# SCH_AdEMNEA-MAK_2024-02-09.net
KiCad netlist of a schematic drawn in EasyEDA
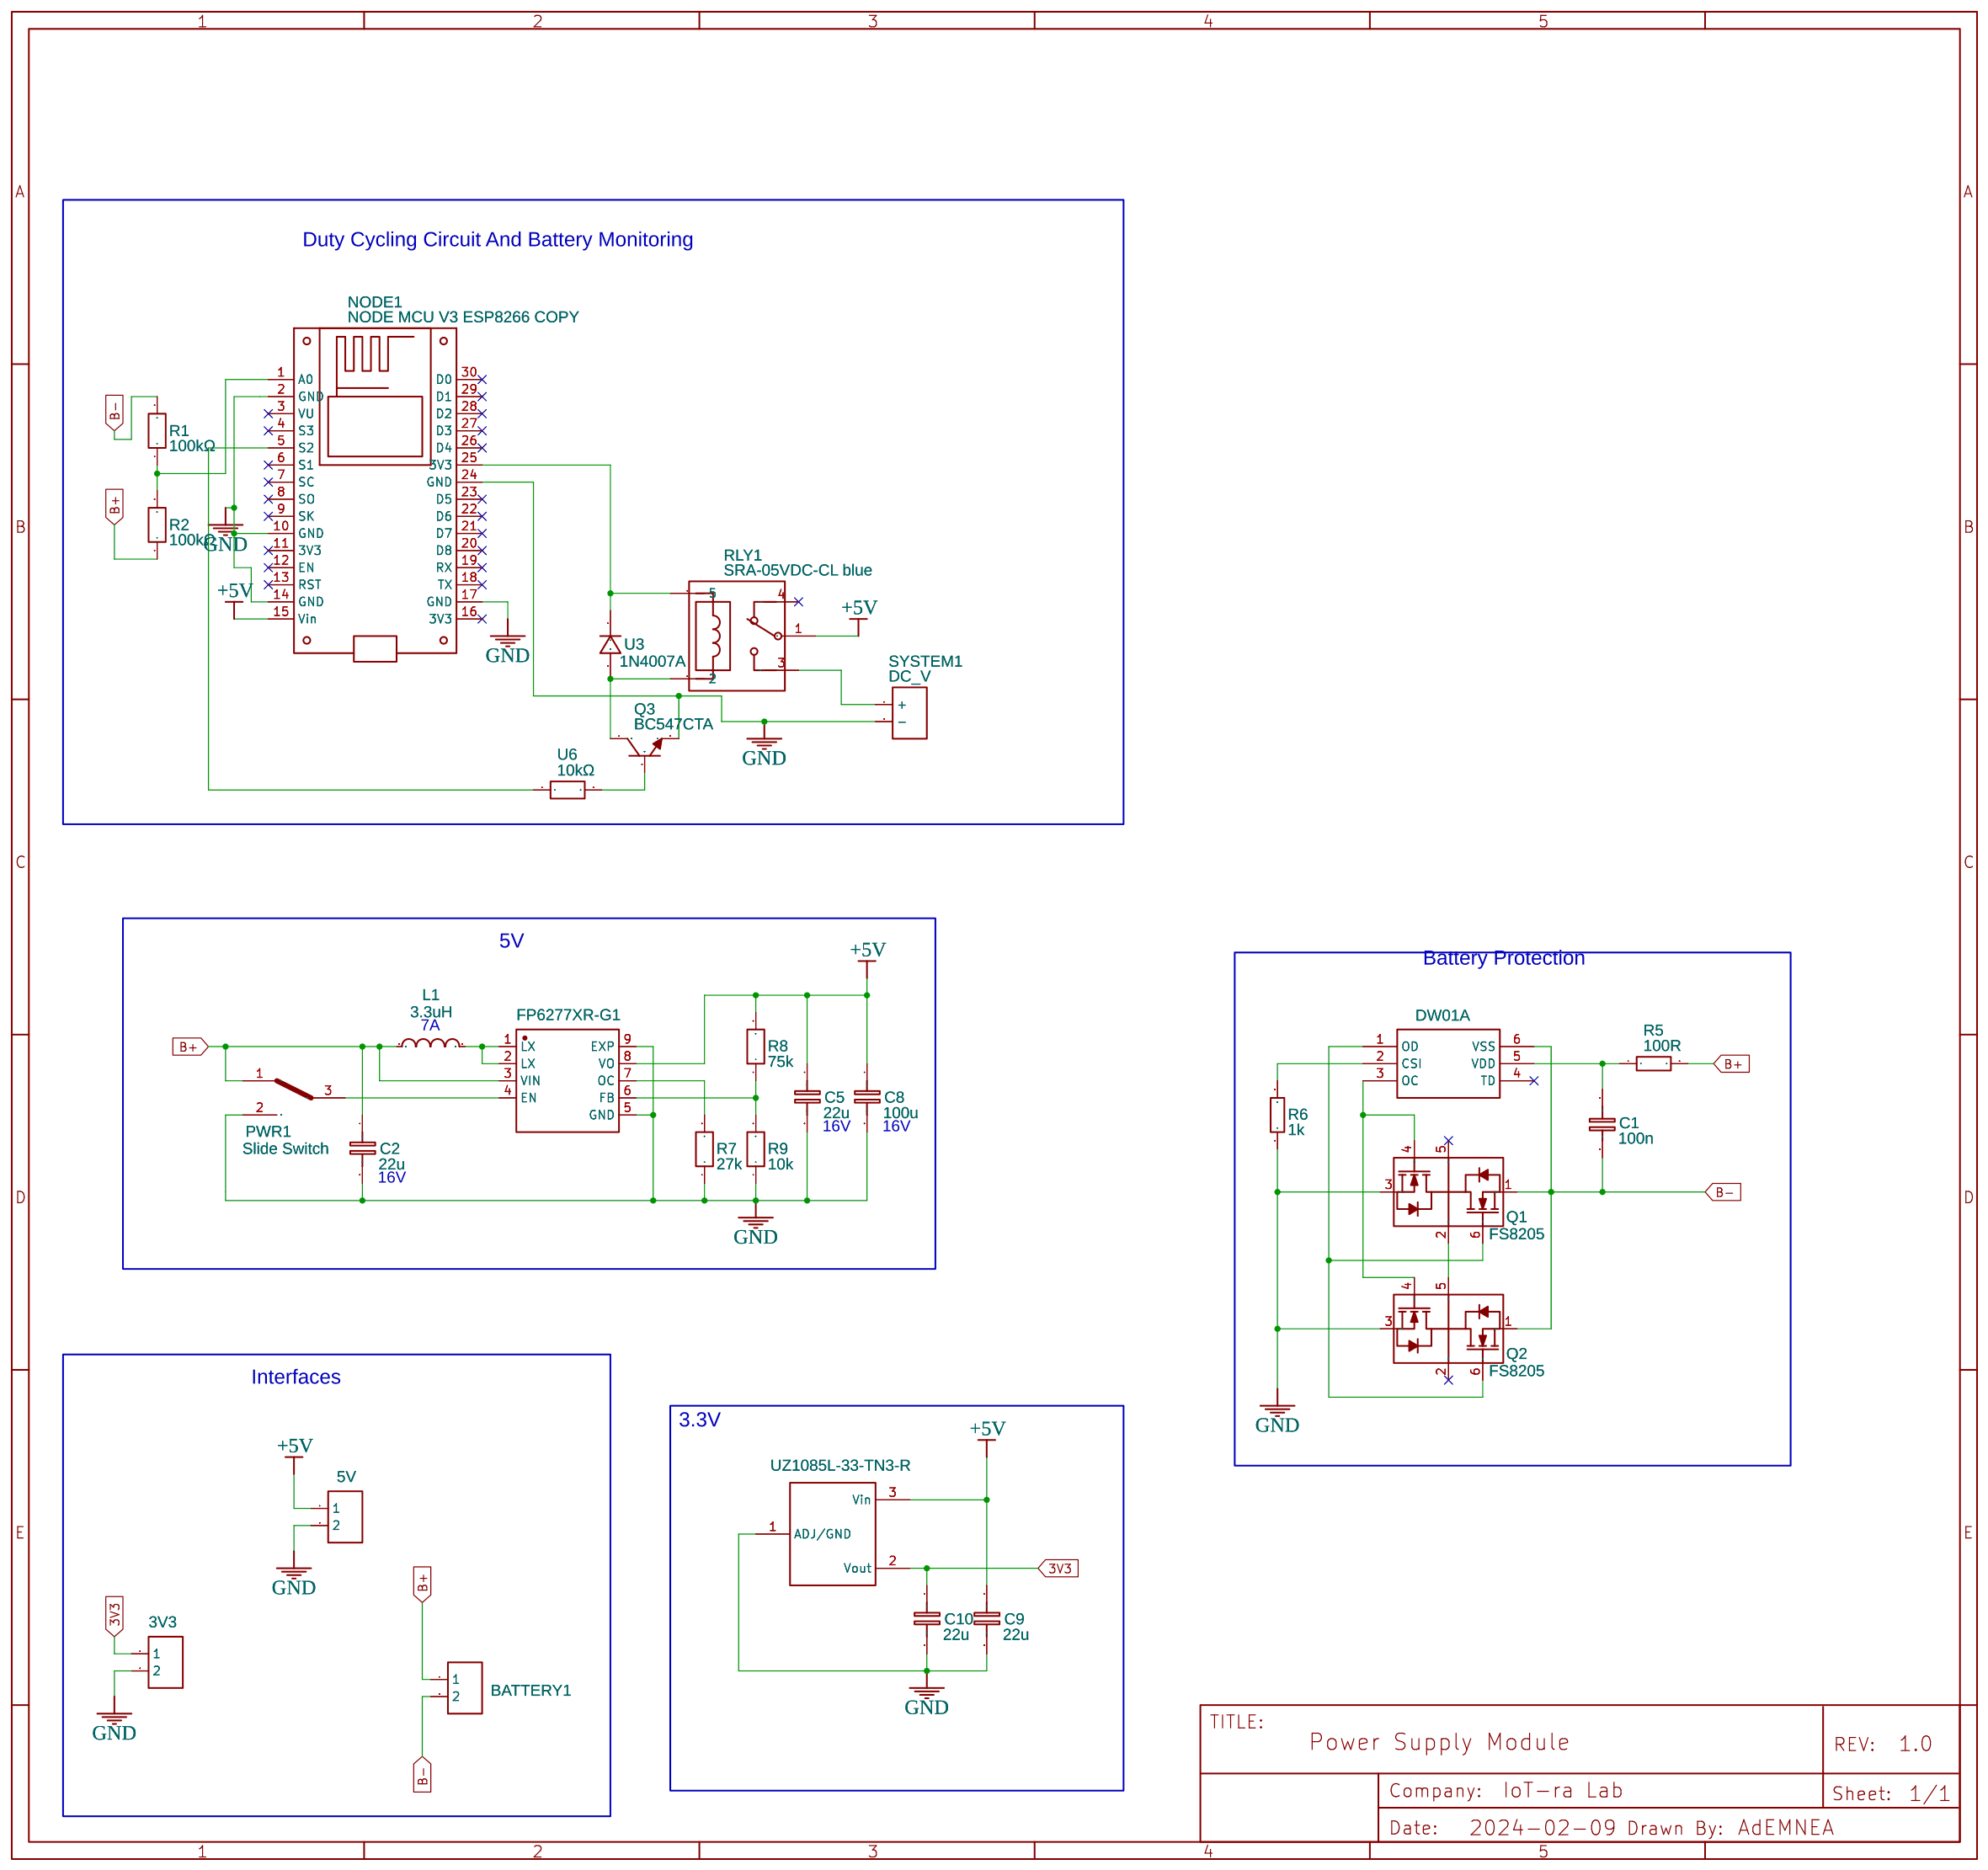
[diagram p0: schematic sheet]

(export (version "E")
  (design (tool "Eeschema 10.0.6"))
  (components
    (comp (ref "3V3")
      (value "Connector")
      (fields (field (name "Manufacturer Part") "2.54-1*2PFemale") (field (name "Manufacturer") "BOOMELE"))
      (libsource (lib "") (part "Unknown_80_-110"))
    )
    (comp (ref "5V")
      (value "Connector")
      (fields (field (name "Manufacturer Part") "2.54-1*2PFemale") (field (name "Manufacturer") "BOOMELE"))
      (libsource (lib "") (part "Unknown_185_-195"))
    )
    (comp (ref "BATTERY1")
      (value "Connector")
      (fields (field (name "Manufacturer Part") "2.54-1*2PFemale") (field (name "Manufacturer") "BOOMELE"))
      (libsource (lib "") (part "Unknown_255_-95"))
    )
    (comp (ref "C1")
      (value "100n")
      (fields (field (name "Manufacturer Part") "CC0805KRX7R9BB104") (field (name "Manufacturer") "YAGEO"))
      (libsource (lib "") (part "Cap_0805_EU_2"))
    )
    (comp (ref "C2")
      (value "22u")
      (fields (field (name "Manufacturer Part") "CL21A226MAQNNNE") (field (name "Manufacturer") "SAMSUNG"))
      (libsource (lib "") (part "Cap_0805_EU"))
    )
    (comp (ref "C5")
      (value "22u")
      (fields (field (name "Manufacturer Part") "CL21A226MAQNNNE") (field (name "Manufacturer") "SAMSUNG"))
      (libsource (lib "") (part "Cap_0805_EU"))
    )
    (comp (ref "C8")
      (value "100u")
      (fields (field (name "Manufacturer Part") "CL31A107MPHNNNE") (field (name "Manufacturer") "SAMSUNG"))
      (libsource (lib "") (part "Cap_0805_EU"))
    )
    (comp (ref "C9")
      (value "22u")
      (fields (field (name "Manufacturer Part") "CL21A226MAQNNNE") (field (name "Manufacturer") "SAMSUNG"))
      (libsource (lib "") (part "Cap_0805_EU_1"))
    )
    (comp (ref "C10")
      (value "22u")
      (fields (field (name "Manufacturer Part") "CL21A226MAQNNNE") (field (name "Manufacturer") "SAMSUNG"))
      (libsource (lib "") (part "Cap_0805_EU_1"))
    )
    (comp (ref "L1")
      (value "3.3uH")
      (fields (field (name "Manufacturer Part") "JSHC0650H-3R3M-G") (field (name "Manufacturer") "Jinlai"))
      (libsource (lib "") (part "JSHC0650H-3R3M-G"))
    )
    (comp (ref "NODE1")
      (value "NODE MCU V3 ESP8266 COPY")
      (libsource (lib "") (part "NODE MCU V3 ESP8266 COPY"))
    )
    (comp (ref "PWR1")
      (value "Slide Switch")
      (fields (field (name "Manufacturer Part") "New SchematicLib"))
      (libsource (lib "") (part "Unknown_160_-440"))
    )
    (comp (ref "Q1")
      (value "FS8205")
      (fields (field (name "Manufacturer") "FORTUNE"))
      (libsource (lib "") (part "FS8205"))
    )
    (comp (ref "Q2")
      (value "FS8205")
      (fields (field (name "Manufacturer") "FORTUNE"))
      (libsource (lib "") (part "FS8205"))
    )
    (comp (ref "Q3")
      (value "BC547CTA")
      (fields (field (name "Manufacturer") "onsemi(安森美)"))
      (libsource (lib "") (part "BC547CTA"))
    )
    (comp (ref "R1")
      (value "100kΩ")
      (fields
        (field (name "Manufacturer Part") "RNF14FAE100K")
        (field (name "Manufacturer") "SEI(Stackpole Electronics Inc.)")
      )
      (libsource (lib "") (part "RNF14FAE100K"))
    )
    (comp (ref "R2")
      (value "100kΩ")
      (fields
        (field (name "Manufacturer Part") "RNF14FAE100K")
        (field (name "Manufacturer") "SEI(Stackpole Electronics Inc.)")
      )
      (libsource (lib "") (part "RNF14FAE100K"))
    )
    (comp (ref "R5")
      (value "100R")
      (fields (field (name "Manufacturer Part") "0805W8F1000T5E") (field (name "Manufacturer") "UniOhm"))
      (libsource (lib "") (part "Res_0805(1/8W)_EU_1"))
    )
    (comp (ref "R6")
      (value "1k")
      (fields (field (name "Manufacturer Part") "0805W8F1001T5E") (field (name "Manufacturer") "UniOhm"))
      (libsource (lib "") (part "Res_0805(1/8W)_EU_2"))
    )
    (comp (ref "R7")
      (value "27k")
      (fields (field (name "Manufacturer Part") "0805W8F2702T5E") (field (name "Manufacturer") "UniOhm"))
      (libsource (lib "") (part "Res_0805(1/8W)_EU"))
    )
    (comp (ref "R8")
      (value "75k")
      (fields (field (name "Manufacturer Part") "0805W8F7502T5E") (field (name "Manufacturer") "UniOhm"))
      (libsource (lib "") (part "Res_0805(1/8W)_EU"))
    )
    (comp (ref "R9")
      (value "10k")
      (fields (field (name "Manufacturer Part") "0805W8F1002T5E") (field (name "Manufacturer") "UniOhm"))
      (libsource (lib "") (part "Res_0805(1/8W)_EU"))
    )
    (comp (ref "RLY1")
      (value "SRA-05VDC-CL blue")
      (fields (field (name "Manufacturer Part") "SRA-05VDC-CL") (field (name "Manufacturer") "松乐"))
      (libsource (lib "") (part "SRA-05VDC-CL blue"))
    )
    (comp (ref "SYSTEM1") (value "DC_V") (libsource (lib "") (part "DC_V")))
    (comp (ref "U1")
      (value "FP6277XR-G1")
      (fields (field (name "Manufacturer") "Feeling Technology"))
      (libsource (lib "") (part "FP6277XR-G1"))
    )
    (comp (ref "U2")
      (value "DW01A")
      (fields (field (name "Manufacturer") "FM"))
      (libsource (lib "") (part "Unknown_835_-460"))
    )
    (comp (ref "U3")
      (value "1N4007A")
      (fields (field (name "Manufacturer") "LRC(乐山无线电)"))
      (libsource (lib "") (part "1N4007A"))
    )
    (comp (ref "U4")
      (value "UZ1085L-33-TN3-R")
      (fields (field (name "Manufacturer") "UTC"))
      (libsource (lib "") (part "UZ1085L-33-TN3-R"))
    )
    (comp (ref "U6")
      (value "10kΩ")
      (fields (field (name "Manufacturer Part") "FM0207FTE52-10K") (field (name "Manufacturer") "YAGEO(国巨)"))
      (libsource (lib "") (part "FM0207FTE52-10K"))
    )
  )
  (nets
    (net (code "1") (name "+5V") (class "Default")
      (node (ref "5V") (pin "1") (pinfunction "1_1") (pintype "input"))
      (node (ref "C5") (pin "1") (pinfunction "1_1") (pintype "unspecified"))
      (node (ref "C8") (pin "1") (pinfunction "1_1") (pintype "unspecified"))
      (node (ref "C9") (pin "1") (pinfunction "1_1") (pintype "unspecified"))
      (node (ref "NODE1") (pin "15") (pinfunction "Vin_15") (pintype "unspecified"))
      (node (ref "R8") (pin "2") (pinfunction "2_2") (pintype "unspecified"))
      (node (ref "RLY1") (pin "1") (pinfunction "1_1") (pintype "unspecified"))
      (node (ref "U1") (pin "8") (pinfunction "VO_8") (pintype "unspecified"))
      (node (ref "U4") (pin "3") (pinfunction "Vin_3") (pintype "unspecified"))
    )
    (net (code "2") (name "3V3") (class "Default")
      (node (ref "3V3") (pin "1") (pinfunction "1_1") (pintype "input"))
      (node (ref "C10") (pin "1") (pinfunction "1_1") (pintype "unspecified"))
      (node (ref "U4") (pin "2") (pinfunction "Vout_2") (pintype "unspecified"))
    )
    (net (code "3") (name "B+") (class "Default")
      (node (ref "BATTERY1") (pin "1") (pinfunction "1_1") (pintype "input"))
      (node (ref "C2") (pin "1") (pinfunction "1_1") (pintype "unspecified"))
      (node (ref "L1") (pin "1") (pinfunction "1_1") (pintype "unspecified"))
      (node (ref "PWR1") (pin "1") (pinfunction "1_1") (pintype "unspecified"))
      (node (ref "R2") (pin "1") (pinfunction "1_1") (pintype "unspecified"))
      (node (ref "R5") (pin "2") (pinfunction "2_2") (pintype "unspecified"))
      (node (ref "U1") (pin "3") (pinfunction "VIN_3") (pintype "unspecified"))
    )
    (net (code "4") (name "B-") (class "Default")
      (node (ref "BATTERY1") (pin "2") (pinfunction "2_2") (pintype "input"))
      (node (ref "C1") (pin "1") (pinfunction "1_1") (pintype "unspecified"))
      (node (ref "Q1") (pin "1") (pinfunction "S1_1") (pintype "unspecified"))
      (node (ref "Q2") (pin "1") (pinfunction "S1_1") (pintype "unspecified"))
      (node (ref "R1") (pin "2") (pinfunction "2_2") (pintype "unspecified"))
      (node (ref "U2") (pin "6") (pinfunction "VSS_6") (pintype "unspecified"))
    )
    (net (code "5") (name "GND") (class "Default")
      (node (ref "3V3") (pin "2") (pinfunction "2_2") (pintype "input"))
      (node (ref "5V") (pin "2") (pinfunction "2_2") (pintype "input"))
      (node (ref "C10") (pin "2") (pinfunction "2_2") (pintype "unspecified"))
      (node (ref "C2") (pin "2") (pinfunction "2_2") (pintype "unspecified"))
      (node (ref "C5") (pin "2") (pinfunction "2_2") (pintype "unspecified"))
      (node (ref "C8") (pin "2") (pinfunction "2_2") (pintype "unspecified"))
      (node (ref "C9") (pin "2") (pinfunction "2_2") (pintype "unspecified"))
      (node (ref "NODE1") (pin "10") (pinfunction "GND_10") (pintype "unspecified"))
      (node (ref "NODE1") (pin "14") (pinfunction "GND_14") (pintype "unspecified"))
      (node (ref "NODE1") (pin "17") (pinfunction "GND_17") (pintype "unspecified"))
      (node (ref "NODE1") (pin "2") (pinfunction "GND_2") (pintype "unspecified"))
      (node (ref "NODE1") (pin "24") (pinfunction "GND_24") (pintype "unspecified"))
      (node (ref "PWR1") (pin "2") (pinfunction "2_2") (pintype "unspecified"))
      (node (ref "Q1") (pin "3") (pinfunction "S2_3") (pintype "unspecified"))
      (node (ref "Q2") (pin "3") (pinfunction "S2_3") (pintype "unspecified"))
      (node (ref "Q3") (pin "3") (pinfunction "E_3") (pintype "input"))
      (node (ref "R6") (pin "1") (pinfunction "1_1") (pintype "unspecified"))
      (node (ref "R7") (pin "1") (pinfunction "1_1") (pintype "unspecified"))
      (node (ref "R9") (pin "1") (pinfunction "1_1") (pintype "unspecified"))
      (node (ref "SYSTEM1") (pin "2") (pinfunction "-_2") (pintype "unspecified"))
      (node (ref "U1") (pin "5") (pinfunction "GND_5") (pintype "unspecified"))
      (node (ref "U1") (pin "9") (pinfunction "EXP_9") (pintype "unspecified"))
      (node (ref "U4") (pin "1") (pinfunction "ADJ/GND_1") (pintype "unspecified"))
    )
    (net (code "6") (name "Net-(L1-Pad2)") (class "Default")
      (node (ref "L1") (pin "2") (pinfunction "2_2") (pintype "unspecified"))
      (node (ref "U1") (pin "1") (pinfunction "LX_1") (pintype "unspecified"))
      (node (ref "U1") (pin "2") (pinfunction "LX_2") (pintype "unspecified"))
    )
    (net (code "7") (name "Net-(NODE1-3V3-Pad25)") (class "Default")
      (node (ref "NODE1") (pin "25") (pinfunction "3V3_25") (pintype "unspecified"))
      (node (ref "RLY1") (pin "5") (pinfunction "5_5") (pintype "unspecified"))
      (node (ref "U3") (pin "1") (pinfunction "1_1") (pintype "unspecified"))
    )
    (net (code "8") (name "Net-(NODE1-A0)") (class "Default")
      (node (ref "NODE1") (pin "1") (pinfunction "A0_1") (pintype "unspecified"))
      (node (ref "R1") (pin "1") (pinfunction "1_1") (pintype "unspecified"))
      (node (ref "R2") (pin "2") (pinfunction "2_2") (pintype "unspecified"))
    )
    (net (code "9") (name "Net-(NODE1-S2)") (class "Default")
      (node (ref "NODE1") (pin "5") (pinfunction "S2_5") (pintype "unspecified"))
      (node (ref "U6") (pin "1") (pinfunction "1_1") (pintype "unspecified"))
    )
    (net (code "10") (name "Net-(Q1-D12-Pad2)") (class "Default")
      (node (ref "Q1") (pin "2") (pinfunction "D12_2") (pintype "unspecified"))
      (node (ref "Q2") (pin "5") (pinfunction "D12_5") (pintype "unspecified"))
    )
    (net (code "11") (name "Net-(Q1-G1)") (class "Default")
      (node (ref "Q1") (pin "6") (pinfunction "G1_6") (pintype "unspecified"))
      (node (ref "Q2") (pin "6") (pinfunction "G1_6") (pintype "unspecified"))
      (node (ref "U2") (pin "1") (pinfunction "OD_1") (pintype "unspecified"))
    )
    (net (code "12") (name "Net-(Q1-G2)") (class "Default")
      (node (ref "Q1") (pin "4") (pinfunction "G2_4") (pintype "unspecified"))
      (node (ref "Q2") (pin "4") (pinfunction "G2_4") (pintype "unspecified"))
      (node (ref "U2") (pin "3") (pinfunction "OC_3") (pintype "unspecified"))
    )
    (net (code "13") (name "Net-(Q3-B)") (class "Default")
      (node (ref "Q3") (pin "2") (pinfunction "B_2") (pintype "input"))
      (node (ref "U6") (pin "2") (pinfunction "2_2") (pintype "unspecified"))
    )
    (net (code "14") (name "Net-(Q3-C)") (class "Default")
      (node (ref "Q3") (pin "1") (pinfunction "C_1") (pintype "input"))
      (node (ref "RLY1") (pin "2") (pinfunction "2_2") (pintype "unspecified"))
      (node (ref "U3") (pin "2") (pinfunction "2_2") (pintype "unspecified"))
    )
    (net (code "15") (name "Net-(SYSTEM1-+)") (class "Default")
      (node (ref "RLY1") (pin "3") (pinfunction "3_3") (pintype "unspecified"))
      (node (ref "SYSTEM1") (pin "1") (pinfunction "+_1") (pintype "unspecified"))
    )
    (net (code "16") (name "Net-(U1-EN)") (class "Default")
      (node (ref "PWR1") (pin "3") (pinfunction "3_3") (pintype "unspecified"))
      (node (ref "U1") (pin "4") (pinfunction "EN_4") (pintype "unspecified"))
    )
    (net (code "17") (name "Net-(U1-FB)") (class "Default")
      (node (ref "R8") (pin "1") (pinfunction "1_1") (pintype "unspecified"))
      (node (ref "R9") (pin "2") (pinfunction "2_2") (pintype "unspecified"))
      (node (ref "U1") (pin "6") (pinfunction "FB_6") (pintype "unspecified"))
    )
    (net (code "18") (name "Net-(U1-OC)") (class "Default")
      (node (ref "R7") (pin "2") (pinfunction "2_2") (pintype "unspecified"))
      (node (ref "U1") (pin "7") (pinfunction "OC_7") (pintype "unspecified"))
    )
    (net (code "19") (name "Net-(U2-CSI)") (class "Default")
      (node (ref "R6") (pin "2") (pinfunction "2_2") (pintype "unspecified"))
      (node (ref "U2") (pin "2") (pinfunction "CSI_2") (pintype "unspecified"))
    )
    (net (code "20") (name "Net-(U2-VDD)") (class "Default")
      (node (ref "C1") (pin "2") (pinfunction "2_2") (pintype "unspecified"))
      (node (ref "R5") (pin "1") (pinfunction "1_1") (pintype "unspecified"))
      (node (ref "U2") (pin "5") (pinfunction "VDD_5") (pintype "unspecified"))
    )
    (net (code "21") (name "unconnected-(NODE1-3V3-Pad11)") (class "Default")
      (node (ref "NODE1") (pin "11") (pinfunction "3V3_11") (pintype "unspecified+no_connect"))
    )
    (net (code "22") (name "unconnected-(NODE1-3V3-Pad16)") (class "Default")
      (node (ref "NODE1") (pin "16") (pinfunction "3V3_16") (pintype "unspecified+no_connect"))
    )
    (net (code "23") (name "unconnected-(NODE1-D0-Pad30)") (class "Default")
      (node (ref "NODE1") (pin "30") (pinfunction "D0_30") (pintype "unspecified+no_connect"))
    )
    (net (code "24") (name "unconnected-(NODE1-D1-Pad29)") (class "Default")
      (node (ref "NODE1") (pin "29") (pinfunction "D1_29") (pintype "unspecified+no_connect"))
    )
    (net (code "25") (name "unconnected-(NODE1-D2-Pad28)") (class "Default")
      (node (ref "NODE1") (pin "28") (pinfunction "D2_28") (pintype "unspecified+no_connect"))
    )
    (net (code "26") (name "unconnected-(NODE1-D3-Pad27)") (class "Default")
      (node (ref "NODE1") (pin "27") (pinfunction "D3_27") (pintype "unspecified+no_connect"))
    )
    (net (code "27") (name "unconnected-(NODE1-D4-Pad26)") (class "Default")
      (node (ref "NODE1") (pin "26") (pinfunction "D4_26") (pintype "unspecified+no_connect"))
    )
    (net (code "28") (name "unconnected-(NODE1-D5-Pad23)") (class "Default")
      (node (ref "NODE1") (pin "23") (pinfunction "D5_23") (pintype "unspecified+no_connect"))
    )
    (net (code "29") (name "unconnected-(NODE1-D6-Pad22)") (class "Default")
      (node (ref "NODE1") (pin "22") (pinfunction "D6_22") (pintype "unspecified+no_connect"))
    )
    (net (code "30") (name "unconnected-(NODE1-D7-Pad21)") (class "Default")
      (node (ref "NODE1") (pin "21") (pinfunction "D7_21") (pintype "unspecified+no_connect"))
    )
    (net (code "31") (name "unconnected-(NODE1-D8-Pad20)") (class "Default")
      (node (ref "NODE1") (pin "20") (pinfunction "D8_20") (pintype "unspecified+no_connect"))
    )
    (net (code "32") (name "unconnected-(NODE1-EN-Pad12)") (class "Default")
      (node (ref "NODE1") (pin "12") (pinfunction "EN_12") (pintype "unspecified+no_connect"))
    )
    (net (code "33") (name "unconnected-(NODE1-RST-Pad13)") (class "Default")
      (node (ref "NODE1") (pin "13") (pinfunction "RST_13") (pintype "unspecified+no_connect"))
    )
    (net (code "34") (name "unconnected-(NODE1-RX-Pad19)") (class "Default")
      (node (ref "NODE1") (pin "19") (pinfunction "RX_19") (pintype "unspecified+no_connect"))
    )
    (net (code "35") (name "unconnected-(NODE1-S1-Pad6)") (class "Default")
      (node (ref "NODE1") (pin "6") (pinfunction "S1_6") (pintype "unspecified+no_connect"))
    )
    (net (code "36") (name "unconnected-(NODE1-S3-Pad4)") (class "Default")
      (node (ref "NODE1") (pin "4") (pinfunction "S3_4") (pintype "unspecified+no_connect"))
    )
    (net (code "37") (name "unconnected-(NODE1-SC-Pad7)") (class "Default")
      (node (ref "NODE1") (pin "7") (pinfunction "SC_7") (pintype "unspecified+no_connect"))
    )
    (net (code "38") (name "unconnected-(NODE1-SK-Pad9)") (class "Default")
      (node (ref "NODE1") (pin "9") (pinfunction "SK_9") (pintype "unspecified+no_connect"))
    )
    (net (code "39") (name "unconnected-(NODE1-SO-Pad8)") (class "Default")
      (node (ref "NODE1") (pin "8") (pinfunction "SO_8") (pintype "unspecified+no_connect"))
    )
    (net (code "40") (name "unconnected-(NODE1-TX-Pad18)") (class "Default")
      (node (ref "NODE1") (pin "18") (pinfunction "TX_18") (pintype "unspecified+no_connect"))
    )
    (net (code "41") (name "unconnected-(NODE1-VU-Pad3)") (class "Default")
      (node (ref "NODE1") (pin "3") (pinfunction "VU_3") (pintype "unspecified+no_connect"))
    )
    (net (code "42") (name "unconnected-(Q1-D12-Pad5)") (class "Default")
      (node (ref "Q1") (pin "5") (pinfunction "D12_5") (pintype "unspecified+no_connect"))
    )
    (net (code "43") (name "unconnected-(Q2-D12-Pad2)") (class "Default")
      (node (ref "Q2") (pin "2") (pinfunction "D12_2") (pintype "unspecified+no_connect"))
    )
    (net (code "44") (name "unconnected-(RLY1-Pad4)") (class "Default")
      (node (ref "RLY1") (pin "4") (pinfunction "4_4") (pintype "unspecified+no_connect"))
    )
    (net (code "45") (name "unconnected-(U2-TD-Pad4)") (class "Default")
      (node (ref "U2") (pin "4") (pinfunction "TD_4") (pintype "unspecified+no_connect"))
    )
  )
)
